# esp12e_adaptor.net
KiCad netlist of a schematic drawn in Altium Designer
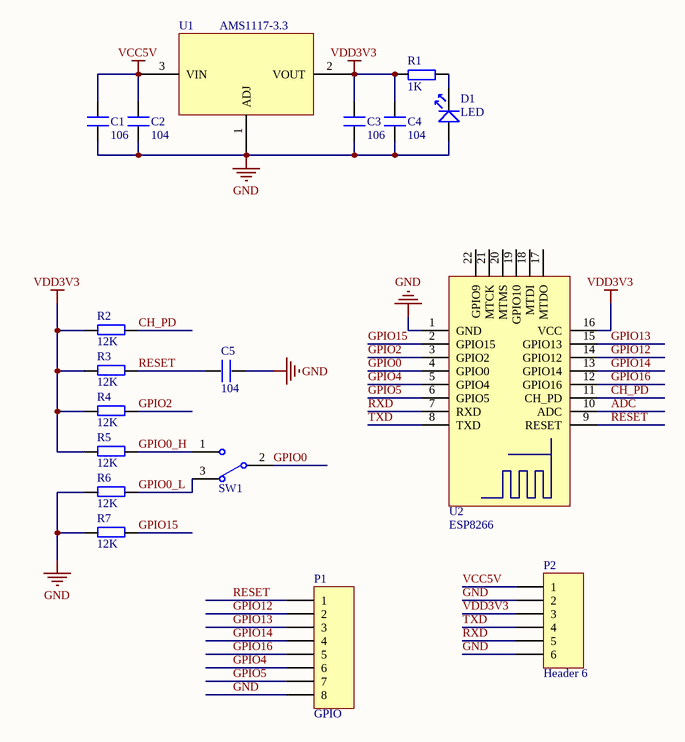
[diagram p0: esp12e_adaptor.SchDoc]

(export (version "E")
  (design (tool "Eeschema 10.0.6"))
  (components
    (comp (ref "C1") (value "106") (footprint "0603P") (libsource (lib "ESP8266V1.2") (part "C")))
    (comp (ref "C2") (value "104") (footprint "0603P") (libsource (lib "ESP8266V1.2") (part "C")))
    (comp (ref "C3") (value "106") (footprint "0603P") (libsource (lib "ESP8266V1.2") (part "C")))
    (comp (ref "C4") (value "104") (footprint "0603P") (libsource (lib "ESP8266V1.2") (part "C")))
    (comp (ref "C5") (value "104") (footprint "0603P") (libsource (lib "ESP8266V1.2") (part "C")))
    (comp (ref "D1") (value "LED") (footprint "SMDLED") (libsource (lib "ESP8266V1.2") (part "LED")))
    (comp (ref "P1")
      (value "GPIO")
      (footprint "HDR1X8")
      (description "Header, 8-Pin")
      (fields (field (name "PUBLISHER") "Altium Limited"))
      (libsource (lib "ESP8266V1.2") (part "Header 8"))
    )
    (comp (ref "P2")
      (value "Header 6")
      (footprint "HDR1X6")
      (description "Header, 6-Pin")
      (fields (field (name "PUBLISHER") "Altium Limited"))
      (libsource (lib "ESP8266V1.2") (part "Header 6"))
    )
    (comp (ref "R1") (value "1K") (footprint "0603P") (libsource (lib "ESP8266V1.2") (part "R")))
    (comp (ref "R2") (value "12K") (footprint "0603P") (libsource (lib "ESP8266V1.2") (part "R")))
    (comp (ref "R3") (value "12K") (footprint "0603P") (libsource (lib "ESP8266V1.2") (part "R")))
    (comp (ref "R4") (value "12K") (footprint "0603P") (libsource (lib "ESP8266V1.2") (part "R")))
    (comp (ref "R5") (value "12K") (footprint "0603P") (libsource (lib "ESP8266V1.2") (part "R")))
    (comp (ref "R6") (value "12K") (footprint "0603P") (libsource (lib "ESP8266V1.2") (part "R")))
    (comp (ref "R7") (value "12K") (footprint "0603P") (libsource (lib "ESP8266V1.2") (part "R")))
    (comp (ref "SW1") (value "SW-SPDT") (footprint "HDR1X3") (libsource (lib "ESP8266V1.2") (part "SW-SPDT")))
    (comp (ref "U1")
      (value "AMS1117-3.3")
      (footprint "SOT223_L")
      (libsource (lib "ESP8266V1.2") (part "AMS1117-3.3"))
    )
    (comp (ref "U2") (value "ESP8266") (footprint "ESP8266") (libsource (lib "ESP8266V1.2") (part "ESP8266")))
  )
  (nets
    (net (code "1") (name "/ADC") (class "Default")
      (node (ref "U2") (pin "10") (pinfunction "ADC_10") (pintype "passive"))
    )
    (net (code "2") (name "/CH_PD") (class "Default")
      (node (ref "R2") (pin "1") (pintype "passive"))
      (node (ref "U2") (pin "11") (pinfunction "CH_PD_11") (pintype "passive"))
    )
    (net (code "3") (name "/GPIO0") (class "Default")
      (node (ref "SW1") (pin "2") (pinfunction "2_2") (pintype "passive"))
      (node (ref "U2") (pin "4") (pinfunction "GPIO0_4") (pintype "passive"))
    )
    (net (code "4") (name "/GPIO0_H") (class "Default")
      (node (ref "R5") (pin "1") (pintype "passive"))
      (node (ref "SW1") (pin "1") (pinfunction "1_1") (pintype "passive"))
    )
    (net (code "5") (name "/GPIO0_L") (class "Default")
      (node (ref "R6") (pin "1") (pintype "passive"))
      (node (ref "SW1") (pin "3") (pinfunction "3_3") (pintype "passive"))
    )
    (net (code "6") (name "/GPIO2") (class "Default")
      (node (ref "R4") (pin "1") (pintype "passive"))
      (node (ref "U2") (pin "3") (pinfunction "GPIO2_3") (pintype "passive"))
    )
    (net (code "7") (name "/GPIO4") (class "Default")
      (node (ref "P1") (pin "6") (pinfunction "6_6") (pintype "passive"))
      (node (ref "U2") (pin "5") (pinfunction "GPIO4_5") (pintype "passive"))
    )
    (net (code "8") (name "/GPIO5") (class "Default")
      (node (ref "P1") (pin "7") (pinfunction "7_7") (pintype "passive"))
      (node (ref "U2") (pin "6") (pinfunction "GPIO5_6") (pintype "passive"))
    )
    (net (code "9") (name "/GPIO12") (class "Default")
      (node (ref "P1") (pin "2") (pinfunction "2_2") (pintype "passive"))
      (node (ref "U2") (pin "14") (pinfunction "GPIO12_14") (pintype "passive"))
    )
    (net (code "10") (name "/GPIO13") (class "Default")
      (node (ref "P1") (pin "3") (pinfunction "3_3") (pintype "passive"))
      (node (ref "U2") (pin "15") (pinfunction "GPIO13_15") (pintype "passive"))
    )
    (net (code "11") (name "/GPIO14") (class "Default")
      (node (ref "P1") (pin "4") (pinfunction "4_4") (pintype "passive"))
      (node (ref "U2") (pin "13") (pinfunction "GPIO14_13") (pintype "passive"))
    )
    (net (code "12") (name "/GPIO15") (class "Default")
      (node (ref "R7") (pin "1") (pintype "passive"))
      (node (ref "U2") (pin "2") (pinfunction "GPIO15_2") (pintype "passive"))
    )
    (net (code "13") (name "/GPIO16") (class "Default")
      (node (ref "P1") (pin "5") (pinfunction "5_5") (pintype "passive"))
      (node (ref "U2") (pin "12") (pinfunction "GPIO16_12") (pintype "passive"))
    )
    (net (code "14") (name "/RESET") (class "Default")
      (node (ref "C5") (pin "1") (pintype "passive"))
      (node (ref "P1") (pin "1") (pinfunction "1_1") (pintype "passive"))
      (node (ref "R3") (pin "1") (pintype "passive"))
      (node (ref "U2") (pin "9") (pinfunction "RESET_9") (pintype "passive"))
    )
    (net (code "15") (name "/RXD") (class "Default")
      (node (ref "P2") (pin "5") (pinfunction "5_5") (pintype "passive"))
      (node (ref "U2") (pin "7") (pinfunction "RXD_7") (pintype "passive"))
    )
    (net (code "16") (name "/TXD") (class "Default")
      (node (ref "P2") (pin "4") (pinfunction "4_4") (pintype "passive"))
      (node (ref "U2") (pin "8") (pinfunction "TXD_8") (pintype "passive"))
    )
    (net (code "17") (name "GND") (class "Default")
      (node (ref "C1") (pin "1") (pintype "passive"))
      (node (ref "C2") (pin "1") (pintype "passive"))
      (node (ref "C3") (pin "1") (pintype "passive"))
      (node (ref "C4") (pin "1") (pintype "passive"))
      (node (ref "C5") (pin "2") (pintype "passive"))
      (node (ref "D1") (pin "1") (pinfunction "1_1") (pintype "passive"))
      (node (ref "P1") (pin "8") (pinfunction "8_8") (pintype "passive"))
      (node (ref "P2") (pin "2") (pinfunction "2_2") (pintype "passive"))
      (node (ref "P2") (pin "6") (pinfunction "6_6") (pintype "passive"))
      (node (ref "R6") (pin "2") (pintype "passive"))
      (node (ref "R7") (pin "2") (pintype "passive"))
      (node (ref "U1") (pin "1") (pinfunction "ADJ_1") (pintype "passive"))
      (node (ref "U2") (pin "1") (pinfunction "GND_1") (pintype "open_emitter"))
    )
    (net (code "18") (name "Net-(D1-Pad2)") (class "Default")
      (node (ref "D1") (pin "2") (pinfunction "2_2") (pintype "passive"))
      (node (ref "R1") (pin "2") (pintype "passive"))
    )
    (net (code "19") (name "VCC5V") (class "Default")
      (node (ref "C1") (pin "2") (pintype "passive"))
      (node (ref "C2") (pin "2") (pintype "passive"))
      (node (ref "P2") (pin "1") (pinfunction "1_1") (pintype "passive"))
      (node (ref "U1") (pin "3") (pinfunction "VIN_3") (pintype "passive"))
    )
    (net (code "20") (name "VDD3V3") (class "Default")
      (node (ref "C3") (pin "2") (pintype "passive"))
      (node (ref "C4") (pin "2") (pintype "passive"))
      (node (ref "P2") (pin "3") (pinfunction "3_3") (pintype "passive"))
      (node (ref "R1") (pin "1") (pintype "passive"))
      (node (ref "R2") (pin "2") (pintype "passive"))
      (node (ref "R3") (pin "2") (pintype "passive"))
      (node (ref "R4") (pin "2") (pintype "passive"))
      (node (ref "R5") (pin "2") (pintype "passive"))
      (node (ref "U1") (pin "2") (pinfunction "VOUT_2") (pintype "passive"))
      (node (ref "U2") (pin "16") (pinfunction "VCC_16") (pintype "passive"))
    )
    (net (code "21") (name "unconnected-(U2-GPIO9-Pad22)") (class "Default")
      (node (ref "U2") (pin "22") (pinfunction "GPIO9_22") (pintype "passive"))
    )
    (net (code "22") (name "unconnected-(U2-GPIO10-Pad19)") (class "Default")
      (node (ref "U2") (pin "19") (pinfunction "GPIO10_19") (pintype "passive"))
    )
    (net (code "23") (name "unconnected-(U2-MTCK-Pad21)") (class "Default")
      (node (ref "U2") (pin "21") (pinfunction "MTCK_21") (pintype "passive"))
    )
    (net (code "24") (name "unconnected-(U2-MTDI-Pad18)") (class "Default")
      (node (ref "U2") (pin "18") (pinfunction "MTDI_18") (pintype "passive"))
    )
    (net (code "25") (name "unconnected-(U2-MTDO-Pad17)") (class "Default")
      (node (ref "U2") (pin "17") (pinfunction "MTDO_17") (pintype "passive"))
    )
    (net (code "26") (name "unconnected-(U2-MTMS-Pad20)") (class "Default")
      (node (ref "U2") (pin "20") (pinfunction "MTMS_20") (pintype "passive"))
    )
  )
)
